# ServoController.net
KiCad netlist of a schematic drawn in Altium Designer
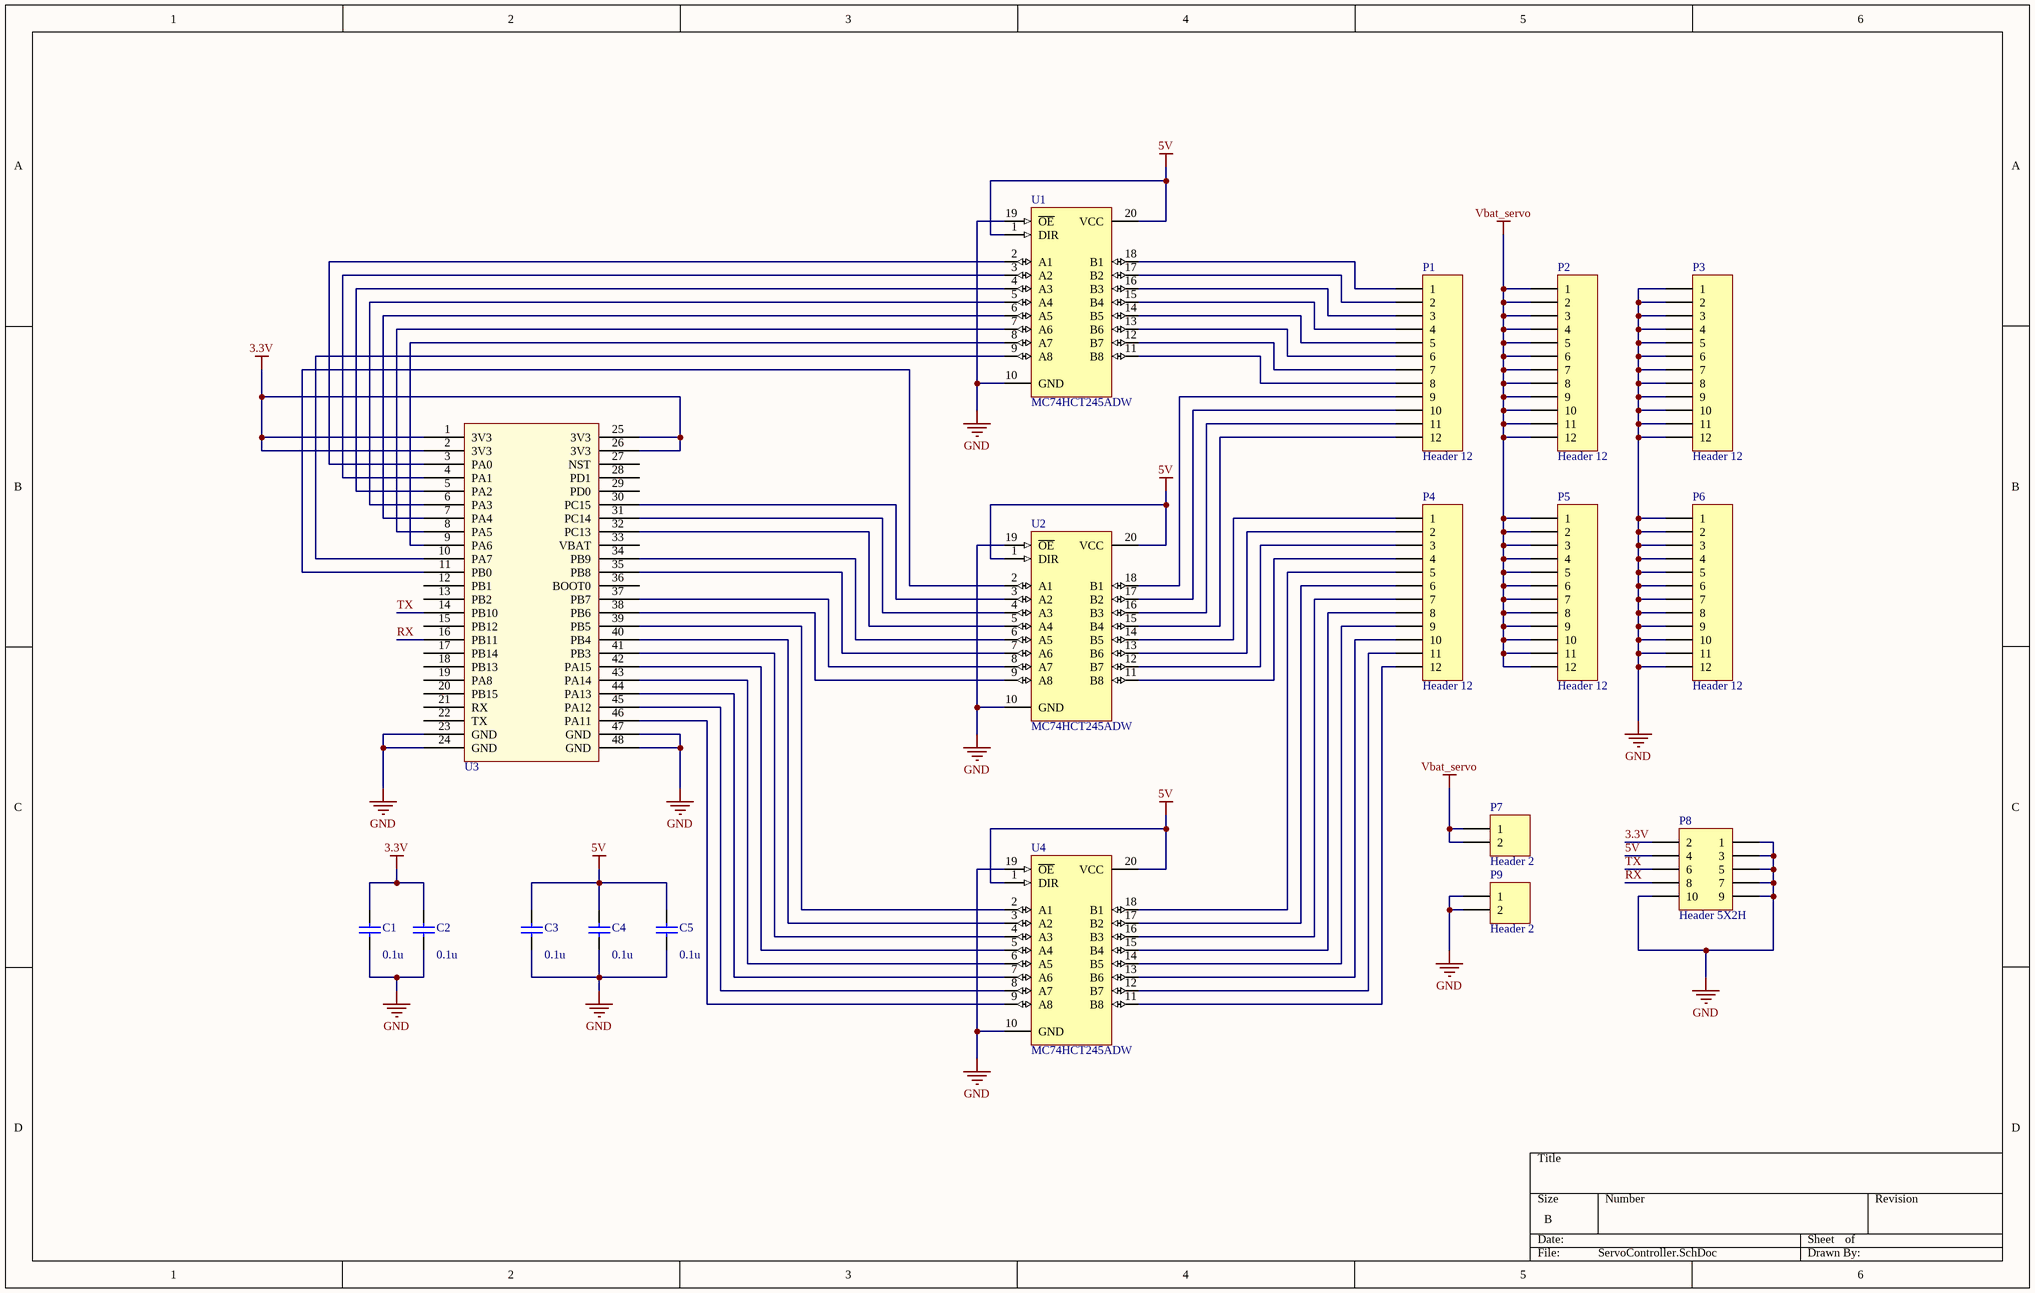
[diagram p0: ServoController.SchDoc]

(export (version "E")
  (design (tool "Eeschema 10.0.6"))
  (components
    (comp (ref "C1")
      (value "0.1u")
      (footprint "C1206")
      (description "Capacitor (Semiconductor SIM Model)")
      (fields (field (name "Comment") "Cap Semi") (field (name "PUBLISHER") "Altium Limited"))
      (libsource (lib "Miscellaneous Devices") (part "Cap Semi"))
    )
    (comp (ref "C2")
      (value "0.1u")
      (footprint "C1206")
      (description "Capacitor (Semiconductor SIM Model)")
      (fields (field (name "Comment") "Cap Semi") (field (name "PUBLISHER") "Altium Limited"))
      (libsource (lib "Miscellaneous Devices") (part "Cap Semi"))
    )
    (comp (ref "C3")
      (value "0.1u")
      (footprint "C1206")
      (description "Capacitor (Semiconductor SIM Model)")
      (fields (field (name "Comment") "Cap Semi") (field (name "PUBLISHER") "Altium Limited"))
      (libsource (lib "Miscellaneous Devices") (part "Cap Semi"))
    )
    (comp (ref "C4")
      (value "0.1u")
      (footprint "C1206")
      (description "Capacitor (Semiconductor SIM Model)")
      (fields (field (name "Comment") "Cap Semi") (field (name "PUBLISHER") "Altium Limited"))
      (libsource (lib "Miscellaneous Devices") (part "Cap Semi"))
    )
    (comp (ref "C5")
      (value "0.1u")
      (footprint "C1206")
      (description "Capacitor (Semiconductor SIM Model)")
      (fields (field (name "Comment") "Cap Semi") (field (name "PUBLISHER") "Altium Limited"))
      (libsource (lib "Miscellaneous Devices") (part "Cap Semi"))
    )
    (comp (ref "P1")
      (value "Header 12")
      (footprint "HDR1X12")
      (description "Header, 12-Pin")
      (fields (field (name "PUBLISHER") "Altium Limited"))
      (libsource (lib "Miscellaneous Connectors") (part "Header 12"))
    )
    (comp (ref "P2")
      (value "Header 12")
      (footprint "HDR1X12")
      (description "Header, 12-Pin")
      (fields (field (name "PUBLISHER") "Altium Limited"))
      (libsource (lib "Miscellaneous Connectors") (part "Header 12"))
    )
    (comp (ref "P3")
      (value "Header 12")
      (footprint "HDR1X12")
      (description "Header, 12-Pin")
      (fields (field (name "PUBLISHER") "Altium Limited"))
      (libsource (lib "Miscellaneous Connectors") (part "Header 12"))
    )
    (comp (ref "P4")
      (value "Header 12")
      (footprint "HDR1X12")
      (description "Header, 12-Pin")
      (fields (field (name "PUBLISHER") "Altium Limited"))
      (libsource (lib "Miscellaneous Connectors") (part "Header 12"))
    )
    (comp (ref "P5")
      (value "Header 12")
      (footprint "HDR1X12")
      (description "Header, 12-Pin")
      (fields (field (name "PUBLISHER") "Altium Limited"))
      (libsource (lib "Miscellaneous Connectors") (part "Header 12"))
    )
    (comp (ref "P6")
      (value "Header 12")
      (footprint "HDR1X12")
      (description "Header, 12-Pin")
      (fields (field (name "PUBLISHER") "Altium Limited"))
      (libsource (lib "Miscellaneous Connectors") (part "Header 12"))
    )
    (comp (ref "P7")
      (value "Header 2")
      (footprint "HDR1X2")
      (description "Header, 2-Pin")
      (fields (field (name "PUBLISHER") "Altium Limited"))
      (libsource (lib "Miscellaneous Connectors") (part "Header 2"))
    )
    (comp (ref "P8")
      (value "Header 5X2H")
      (footprint "HDR2X5H")
      (description "Header, 5-Pin, Dual row, Right Angle")
      (fields (field (name "PUBLISHER") "Altium Limited"))
      (libsource (lib "Miscellaneous Connectors") (part "Header 5X2H"))
    )
    (comp (ref "P9")
      (value "Header 2")
      (footprint "HDR1X2")
      (description "Header, 2-Pin")
      (fields (field (name "PUBLISHER") "Altium Limited"))
      (libsource (lib "Miscellaneous Connectors") (part "Header 2"))
    )
    (comp (ref "U1")
      (value "MC74HCT245ADW")
      (footprint "751D-05_N")
      (description "Octal 3-State Non-Inverting Bus Transceiver with LSTTL-Compatible Inputs")
      (fields (field (name "PUBLISHER") "Altium Limited"))
      (libsource (lib "ON Semi Interface Line Transceiver") (part "MC74HCT245ADW"))
    )
    (comp (ref "U2")
      (value "MC74HCT245ADW")
      (footprint "751D-05_N")
      (description "Octal 3-State Non-Inverting Bus Transceiver with LSTTL-Compatible Inputs")
      (fields (field (name "PUBLISHER") "Altium Limited"))
      (libsource (lib "ON Semi Interface Line Transceiver") (part "MC74HCT245ADW"))
    )
    (comp (ref "U3")
      (value "STM32F103C8T6_Module")
      (footprint "STM32F103C8T6_Module")
      (libsource (lib "QuadrupedSchLib") (part "STM32F103C8T6_Module"))
    )
    (comp (ref "U4")
      (value "MC74HCT245ADW")
      (footprint "751D-05_N")
      (description "Octal 3-State Non-Inverting Bus Transceiver with LSTTL-Compatible Inputs")
      (fields (field (name "PUBLISHER") "Altium Limited"))
      (libsource (lib "ON Semi Interface Line Transceiver") (part "MC74HCT245ADW"))
    )
  )
  (nets
    (net (code "1") (name "/RX") (class "Default")
      (node (ref "P8") (pin "8") (pinfunction "8_8") (pintype "passive"))
      (node (ref "U3") (pin "16") (pinfunction "PB11_16") (pintype "passive"))
    )
    (net (code "2") (name "/TX") (class "Default")
      (node (ref "P8") (pin "6") (pinfunction "6_6") (pintype "passive"))
      (node (ref "U3") (pin "14") (pinfunction "PB10_14") (pintype "passive"))
    )
    (net (code "3") (name "3.3V") (class "Default")
      (node (ref "C1") (pin "2") (pinfunction "2_2") (pintype "passive"))
      (node (ref "C2") (pin "2") (pinfunction "2_2") (pintype "passive"))
      (node (ref "P8") (pin "2") (pinfunction "2_2") (pintype "passive"))
      (node (ref "U3") (pin "1") (pinfunction "3V3_1") (pintype "passive"))
      (node (ref "U3") (pin "2") (pinfunction "3V3_2") (pintype "passive"))
      (node (ref "U3") (pin "25") (pinfunction "3V3_25") (pintype "passive"))
      (node (ref "U3") (pin "26") (pinfunction "3V3_26") (pintype "passive"))
    )
    (net (code "4") (name "5V") (class "Default")
      (node (ref "C3") (pin "2") (pinfunction "2_2") (pintype "passive"))
      (node (ref "C4") (pin "2") (pinfunction "2_2") (pintype "passive"))
      (node (ref "C5") (pin "2") (pinfunction "2_2") (pintype "passive"))
      (node (ref "P8") (pin "4") (pinfunction "4_4") (pintype "passive"))
      (node (ref "U1") (pin "1") (pinfunction "DIR_1") (pintype "input"))
      (node (ref "U1") (pin "20") (pinfunction "VCC_20") (pintype "power_in"))
      (node (ref "U2") (pin "1") (pinfunction "DIR_1") (pintype "input"))
      (node (ref "U2") (pin "20") (pinfunction "VCC_20") (pintype "power_in"))
      (node (ref "U4") (pin "1") (pinfunction "DIR_1") (pintype "input"))
      (node (ref "U4") (pin "20") (pinfunction "VCC_20") (pintype "power_in"))
    )
    (net (code "5") (name "GND") (class "Default")
      (node (ref "C1") (pin "1") (pinfunction "1_1") (pintype "passive"))
      (node (ref "C2") (pin "1") (pinfunction "1_1") (pintype "passive"))
      (node (ref "C3") (pin "1") (pinfunction "1_1") (pintype "passive"))
      (node (ref "C4") (pin "1") (pinfunction "1_1") (pintype "passive"))
      (node (ref "C5") (pin "1") (pinfunction "1_1") (pintype "passive"))
      (node (ref "P3") (pin "1") (pinfunction "1_1") (pintype "passive"))
      (node (ref "P3") (pin "10") (pinfunction "10_10") (pintype "passive"))
      (node (ref "P3") (pin "11") (pinfunction "11_11") (pintype "passive"))
      (node (ref "P3") (pin "12") (pinfunction "12_12") (pintype "passive"))
      (node (ref "P3") (pin "2") (pinfunction "2_2") (pintype "passive"))
      (node (ref "P3") (pin "3") (pinfunction "3_3") (pintype "passive"))
      (node (ref "P3") (pin "4") (pinfunction "4_4") (pintype "passive"))
      (node (ref "P3") (pin "5") (pinfunction "5_5") (pintype "passive"))
      (node (ref "P3") (pin "6") (pinfunction "6_6") (pintype "passive"))
      (node (ref "P3") (pin "7") (pinfunction "7_7") (pintype "passive"))
      (node (ref "P3") (pin "8") (pinfunction "8_8") (pintype "passive"))
      (node (ref "P3") (pin "9") (pinfunction "9_9") (pintype "passive"))
      (node (ref "P6") (pin "1") (pinfunction "1_1") (pintype "passive"))
      (node (ref "P6") (pin "10") (pinfunction "10_10") (pintype "passive"))
      (node (ref "P6") (pin "11") (pinfunction "11_11") (pintype "passive"))
      (node (ref "P6") (pin "12") (pinfunction "12_12") (pintype "passive"))
      (node (ref "P6") (pin "2") (pinfunction "2_2") (pintype "passive"))
      (node (ref "P6") (pin "3") (pinfunction "3_3") (pintype "passive"))
      (node (ref "P6") (pin "4") (pinfunction "4_4") (pintype "passive"))
      (node (ref "P6") (pin "5") (pinfunction "5_5") (pintype "passive"))
      (node (ref "P6") (pin "6") (pinfunction "6_6") (pintype "passive"))
      (node (ref "P6") (pin "7") (pinfunction "7_7") (pintype "passive"))
      (node (ref "P6") (pin "8") (pinfunction "8_8") (pintype "passive"))
      (node (ref "P6") (pin "9") (pinfunction "9_9") (pintype "passive"))
      (node (ref "P8") (pin "1") (pinfunction "1_1") (pintype "passive"))
      (node (ref "P8") (pin "10") (pinfunction "10_10") (pintype "passive"))
      (node (ref "P8") (pin "3") (pinfunction "3_3") (pintype "passive"))
      (node (ref "P8") (pin "5") (pinfunction "5_5") (pintype "passive"))
      (node (ref "P8") (pin "7") (pinfunction "7_7") (pintype "passive"))
      (node (ref "P8") (pin "9") (pinfunction "9_9") (pintype "passive"))
      (node (ref "P9") (pin "1") (pinfunction "1_1") (pintype "passive"))
      (node (ref "P9") (pin "2") (pinfunction "2_2") (pintype "passive"))
      (node (ref "U1") (pin "10") (pinfunction "GND_10") (pintype "power_in"))
      (node (ref "U1") (pin "19") (pinfunction "~{OE}_19") (pintype "input"))
      (node (ref "U2") (pin "10") (pinfunction "GND_10") (pintype "power_in"))
      (node (ref "U2") (pin "19") (pinfunction "~{OE}_19") (pintype "input"))
      (node (ref "U3") (pin "23") (pinfunction "GND_23") (pintype "passive"))
      (node (ref "U3") (pin "24") (pinfunction "GND_24") (pintype "passive"))
      (node (ref "U3") (pin "47") (pinfunction "GND_47") (pintype "passive"))
      (node (ref "U3") (pin "48") (pinfunction "GND_48") (pintype "passive"))
      (node (ref "U4") (pin "10") (pinfunction "GND_10") (pintype "power_in"))
      (node (ref "U4") (pin "19") (pinfunction "~{OE}_19") (pintype "input"))
    )
    (net (code "6") (name "Net-(U1-A1)") (class "Default")
      (node (ref "U1") (pin "2") (pinfunction "A1_2") (pintype "bidirectional"))
      (node (ref "U3") (pin "3") (pinfunction "PA0_3") (pintype "passive"))
    )
    (net (code "7") (name "Net-(U1-A2)") (class "Default")
      (node (ref "U1") (pin "3") (pinfunction "A2_3") (pintype "bidirectional"))
      (node (ref "U3") (pin "4") (pinfunction "PA1_4") (pintype "passive"))
    )
    (net (code "8") (name "Net-(U1-A3)") (class "Default")
      (node (ref "U1") (pin "4") (pinfunction "A3_4") (pintype "bidirectional"))
      (node (ref "U3") (pin "5") (pinfunction "PA2_5") (pintype "passive"))
    )
    (net (code "9") (name "Net-(U1-A4)") (class "Default")
      (node (ref "U1") (pin "5") (pinfunction "A4_5") (pintype "bidirectional"))
      (node (ref "U3") (pin "6") (pinfunction "PA3_6") (pintype "passive"))
    )
    (net (code "10") (name "Net-(U1-A5)") (class "Default")
      (node (ref "U1") (pin "6") (pinfunction "A5_6") (pintype "bidirectional"))
      (node (ref "U3") (pin "7") (pinfunction "PA4_7") (pintype "passive"))
    )
    (net (code "11") (name "Net-(U1-A6)") (class "Default")
      (node (ref "U1") (pin "7") (pinfunction "A6_7") (pintype "bidirectional"))
      (node (ref "U3") (pin "8") (pinfunction "PA5_8") (pintype "passive"))
    )
    (net (code "12") (name "Net-(U1-A7)") (class "Default")
      (node (ref "U1") (pin "8") (pinfunction "A7_8") (pintype "bidirectional"))
      (node (ref "U3") (pin "9") (pinfunction "PA6_9") (pintype "passive"))
    )
    (net (code "13") (name "Net-(U1-A8)") (class "Default")
      (node (ref "U1") (pin "9") (pinfunction "A8_9") (pintype "bidirectional"))
      (node (ref "U3") (pin "10") (pinfunction "PA7_10") (pintype "passive"))
    )
    (net (code "14") (name "Net-(U1-B1)") (class "Default")
      (node (ref "P1") (pin "1") (pinfunction "1_1") (pintype "passive"))
      (node (ref "U1") (pin "18") (pinfunction "B1_18") (pintype "bidirectional"))
    )
    (net (code "15") (name "Net-(U1-B2)") (class "Default")
      (node (ref "P1") (pin "2") (pinfunction "2_2") (pintype "passive"))
      (node (ref "U1") (pin "17") (pinfunction "B2_17") (pintype "bidirectional"))
    )
    (net (code "16") (name "Net-(U1-B3)") (class "Default")
      (node (ref "P1") (pin "3") (pinfunction "3_3") (pintype "passive"))
      (node (ref "U1") (pin "16") (pinfunction "B3_16") (pintype "bidirectional"))
    )
    (net (code "17") (name "Net-(U1-B4)") (class "Default")
      (node (ref "P1") (pin "4") (pinfunction "4_4") (pintype "passive"))
      (node (ref "U1") (pin "15") (pinfunction "B4_15") (pintype "bidirectional"))
    )
    (net (code "18") (name "Net-(U1-B5)") (class "Default")
      (node (ref "P1") (pin "5") (pinfunction "5_5") (pintype "passive"))
      (node (ref "U1") (pin "14") (pinfunction "B5_14") (pintype "bidirectional"))
    )
    (net (code "19") (name "Net-(U1-B6)") (class "Default")
      (node (ref "P1") (pin "6") (pinfunction "6_6") (pintype "passive"))
      (node (ref "U1") (pin "13") (pinfunction "B6_13") (pintype "bidirectional"))
    )
    (net (code "20") (name "Net-(U1-B7)") (class "Default")
      (node (ref "P1") (pin "7") (pinfunction "7_7") (pintype "passive"))
      (node (ref "U1") (pin "12") (pinfunction "B7_12") (pintype "bidirectional"))
    )
    (net (code "21") (name "Net-(U1-B8)") (class "Default")
      (node (ref "P1") (pin "8") (pinfunction "8_8") (pintype "passive"))
      (node (ref "U1") (pin "11") (pinfunction "B8_11") (pintype "bidirectional"))
    )
    (net (code "22") (name "Net-(U2-A1)") (class "Default")
      (node (ref "U2") (pin "2") (pinfunction "A1_2") (pintype "bidirectional"))
      (node (ref "U3") (pin "11") (pinfunction "PB0_11") (pintype "passive"))
    )
    (net (code "23") (name "Net-(U2-A2)") (class "Default")
      (node (ref "U2") (pin "3") (pinfunction "A2_3") (pintype "bidirectional"))
      (node (ref "U3") (pin "30") (pinfunction "PC15_30") (pintype "passive"))
    )
    (net (code "24") (name "Net-(U2-A3)") (class "Default")
      (node (ref "U2") (pin "4") (pinfunction "A3_4") (pintype "bidirectional"))
      (node (ref "U3") (pin "31") (pinfunction "PC14_31") (pintype "passive"))
    )
    (net (code "25") (name "Net-(U2-A4)") (class "Default")
      (node (ref "U2") (pin "5") (pinfunction "A4_5") (pintype "bidirectional"))
      (node (ref "U3") (pin "32") (pinfunction "PC13_32") (pintype "passive"))
    )
    (net (code "26") (name "Net-(U2-A5)") (class "Default")
      (node (ref "U2") (pin "6") (pinfunction "A5_6") (pintype "bidirectional"))
      (node (ref "U3") (pin "34") (pinfunction "PB9_34") (pintype "passive"))
    )
    (net (code "27") (name "Net-(U2-A6)") (class "Default")
      (node (ref "U2") (pin "7") (pinfunction "A6_7") (pintype "bidirectional"))
      (node (ref "U3") (pin "35") (pinfunction "PB8_35") (pintype "passive"))
    )
    (net (code "28") (name "Net-(U2-A7)") (class "Default")
      (node (ref "U2") (pin "8") (pinfunction "A7_8") (pintype "bidirectional"))
      (node (ref "U3") (pin "37") (pinfunction "PB7_37") (pintype "passive"))
    )
    (net (code "29") (name "Net-(U2-A8)") (class "Default")
      (node (ref "U2") (pin "9") (pinfunction "A8_9") (pintype "bidirectional"))
      (node (ref "U3") (pin "38") (pinfunction "PB6_38") (pintype "passive"))
    )
    (net (code "30") (name "Net-(U2-B1)") (class "Default")
      (node (ref "P1") (pin "9") (pinfunction "9_9") (pintype "passive"))
      (node (ref "U2") (pin "18") (pinfunction "B1_18") (pintype "bidirectional"))
    )
    (net (code "31") (name "Net-(U2-B2)") (class "Default")
      (node (ref "P1") (pin "10") (pinfunction "10_10") (pintype "passive"))
      (node (ref "U2") (pin "17") (pinfunction "B2_17") (pintype "bidirectional"))
    )
    (net (code "32") (name "Net-(U2-B3)") (class "Default")
      (node (ref "P1") (pin "11") (pinfunction "11_11") (pintype "passive"))
      (node (ref "U2") (pin "16") (pinfunction "B3_16") (pintype "bidirectional"))
    )
    (net (code "33") (name "Net-(U2-B4)") (class "Default")
      (node (ref "P1") (pin "12") (pinfunction "12_12") (pintype "passive"))
      (node (ref "U2") (pin "15") (pinfunction "B4_15") (pintype "bidirectional"))
    )
    (net (code "34") (name "Net-(U2-B5)") (class "Default")
      (node (ref "P4") (pin "1") (pinfunction "1_1") (pintype "passive"))
      (node (ref "U2") (pin "14") (pinfunction "B5_14") (pintype "bidirectional"))
    )
    (net (code "35") (name "Net-(U2-B6)") (class "Default")
      (node (ref "P4") (pin "2") (pinfunction "2_2") (pintype "passive"))
      (node (ref "U2") (pin "13") (pinfunction "B6_13") (pintype "bidirectional"))
    )
    (net (code "36") (name "Net-(U2-B7)") (class "Default")
      (node (ref "P4") (pin "3") (pinfunction "3_3") (pintype "passive"))
      (node (ref "U2") (pin "12") (pinfunction "B7_12") (pintype "bidirectional"))
    )
    (net (code "37") (name "Net-(U2-B8)") (class "Default")
      (node (ref "P4") (pin "4") (pinfunction "4_4") (pintype "passive"))
      (node (ref "U2") (pin "11") (pinfunction "B8_11") (pintype "bidirectional"))
    )
    (net (code "38") (name "Net-(U3-PA11)") (class "Default")
      (node (ref "U3") (pin "46") (pinfunction "PA11_46") (pintype "passive"))
      (node (ref "U4") (pin "9") (pinfunction "A8_9") (pintype "bidirectional"))
    )
    (net (code "39") (name "Net-(U3-PA12)") (class "Default")
      (node (ref "U3") (pin "45") (pinfunction "PA12_45") (pintype "passive"))
      (node (ref "U4") (pin "8") (pinfunction "A7_8") (pintype "bidirectional"))
    )
    (net (code "40") (name "Net-(U3-PA13)") (class "Default")
      (node (ref "U3") (pin "44") (pinfunction "PA13_44") (pintype "passive"))
      (node (ref "U4") (pin "7") (pinfunction "A6_7") (pintype "bidirectional"))
    )
    (net (code "41") (name "Net-(U3-PA14)") (class "Default")
      (node (ref "U3") (pin "43") (pinfunction "PA14_43") (pintype "passive"))
      (node (ref "U4") (pin "6") (pinfunction "A5_6") (pintype "bidirectional"))
    )
    (net (code "42") (name "Net-(U3-PA15)") (class "Default")
      (node (ref "U3") (pin "42") (pinfunction "PA15_42") (pintype "passive"))
      (node (ref "U4") (pin "5") (pinfunction "A4_5") (pintype "bidirectional"))
    )
    (net (code "43") (name "Net-(U3-PB3)") (class "Default")
      (node (ref "U3") (pin "41") (pinfunction "PB3_41") (pintype "passive"))
      (node (ref "U4") (pin "4") (pinfunction "A3_4") (pintype "bidirectional"))
    )
    (net (code "44") (name "Net-(U3-PB4)") (class "Default")
      (node (ref "U3") (pin "40") (pinfunction "PB4_40") (pintype "passive"))
      (node (ref "U4") (pin "3") (pinfunction "A2_3") (pintype "bidirectional"))
    )
    (net (code "45") (name "Net-(U3-PB5)") (class "Default")
      (node (ref "U3") (pin "39") (pinfunction "PB5_39") (pintype "passive"))
      (node (ref "U4") (pin "2") (pinfunction "A1_2") (pintype "bidirectional"))
    )
    (net (code "46") (name "Net-(U4-B1)") (class "Default")
      (node (ref "P4") (pin "5") (pinfunction "5_5") (pintype "passive"))
      (node (ref "U4") (pin "18") (pinfunction "B1_18") (pintype "bidirectional"))
    )
    (net (code "47") (name "Net-(U4-B2)") (class "Default")
      (node (ref "P4") (pin "6") (pinfunction "6_6") (pintype "passive"))
      (node (ref "U4") (pin "17") (pinfunction "B2_17") (pintype "bidirectional"))
    )
    (net (code "48") (name "Net-(U4-B3)") (class "Default")
      (node (ref "P4") (pin "7") (pinfunction "7_7") (pintype "passive"))
      (node (ref "U4") (pin "16") (pinfunction "B3_16") (pintype "bidirectional"))
    )
    (net (code "49") (name "Net-(U4-B4)") (class "Default")
      (node (ref "P4") (pin "8") (pinfunction "8_8") (pintype "passive"))
      (node (ref "U4") (pin "15") (pinfunction "B4_15") (pintype "bidirectional"))
    )
    (net (code "50") (name "Net-(U4-B5)") (class "Default")
      (node (ref "P4") (pin "9") (pinfunction "9_9") (pintype "passive"))
      (node (ref "U4") (pin "14") (pinfunction "B5_14") (pintype "bidirectional"))
    )
    (net (code "51") (name "Net-(U4-B6)") (class "Default")
      (node (ref "P4") (pin "10") (pinfunction "10_10") (pintype "passive"))
      (node (ref "U4") (pin "13") (pinfunction "B6_13") (pintype "bidirectional"))
    )
    (net (code "52") (name "Net-(U4-B7)") (class "Default")
      (node (ref "P4") (pin "11") (pinfunction "11_11") (pintype "passive"))
      (node (ref "U4") (pin "12") (pinfunction "B7_12") (pintype "bidirectional"))
    )
    (net (code "53") (name "Net-(U4-B8)") (class "Default")
      (node (ref "P4") (pin "12") (pinfunction "12_12") (pintype "passive"))
      (node (ref "U4") (pin "11") (pinfunction "B8_11") (pintype "bidirectional"))
    )
    (net (code "54") (name "Vbat_servo") (class "Default")
      (node (ref "P2") (pin "1") (pinfunction "1_1") (pintype "passive"))
      (node (ref "P2") (pin "10") (pinfunction "10_10") (pintype "passive"))
      (node (ref "P2") (pin "11") (pinfunction "11_11") (pintype "passive"))
      (node (ref "P2") (pin "12") (pinfunction "12_12") (pintype "passive"))
      (node (ref "P2") (pin "2") (pinfunction "2_2") (pintype "passive"))
      (node (ref "P2") (pin "3") (pinfunction "3_3") (pintype "passive"))
      (node (ref "P2") (pin "4") (pinfunction "4_4") (pintype "passive"))
      (node (ref "P2") (pin "5") (pinfunction "5_5") (pintype "passive"))
      (node (ref "P2") (pin "6") (pinfunction "6_6") (pintype "passive"))
      (node (ref "P2") (pin "7") (pinfunction "7_7") (pintype "passive"))
      (node (ref "P2") (pin "8") (pinfunction "8_8") (pintype "passive"))
      (node (ref "P2") (pin "9") (pinfunction "9_9") (pintype "passive"))
      (node (ref "P5") (pin "1") (pinfunction "1_1") (pintype "passive"))
      (node (ref "P5") (pin "10") (pinfunction "10_10") (pintype "passive"))
      (node (ref "P5") (pin "11") (pinfunction "11_11") (pintype "passive"))
      (node (ref "P5") (pin "12") (pinfunction "12_12") (pintype "passive"))
      (node (ref "P5") (pin "2") (pinfunction "2_2") (pintype "passive"))
      (node (ref "P5") (pin "3") (pinfunction "3_3") (pintype "passive"))
      (node (ref "P5") (pin "4") (pinfunction "4_4") (pintype "passive"))
      (node (ref "P5") (pin "5") (pinfunction "5_5") (pintype "passive"))
      (node (ref "P5") (pin "6") (pinfunction "6_6") (pintype "passive"))
      (node (ref "P5") (pin "7") (pinfunction "7_7") (pintype "passive"))
      (node (ref "P5") (pin "8") (pinfunction "8_8") (pintype "passive"))
      (node (ref "P5") (pin "9") (pinfunction "9_9") (pintype "passive"))
      (node (ref "P7") (pin "1") (pinfunction "1_1") (pintype "passive"))
      (node (ref "P7") (pin "2") (pinfunction "2_2") (pintype "passive"))
    )
    (net (code "55") (name "unconnected-(U3-BOOT0-Pad36)") (class "Default")
      (node (ref "U3") (pin "36") (pinfunction "BOOT0_36") (pintype "passive"))
    )
    (net (code "56") (name "unconnected-(U3-NST-Pad27)") (class "Default")
      (node (ref "U3") (pin "27") (pinfunction "NST_27") (pintype "passive"))
    )
    (net (code "57") (name "unconnected-(U3-PA8-Pad19)") (class "Default")
      (node (ref "U3") (pin "19") (pinfunction "PA8_19") (pintype "passive"))
    )
    (net (code "58") (name "unconnected-(U3-PB1-Pad12)") (class "Default")
      (node (ref "U3") (pin "12") (pinfunction "PB1_12") (pintype "passive"))
    )
    (net (code "59") (name "unconnected-(U3-PB2-Pad13)") (class "Default")
      (node (ref "U3") (pin "13") (pinfunction "PB2_13") (pintype "passive"))
    )
    (net (code "60") (name "unconnected-(U3-PB12-Pad15)") (class "Default")
      (node (ref "U3") (pin "15") (pinfunction "PB12_15") (pintype "passive"))
    )
    (net (code "61") (name "unconnected-(U3-PB13-Pad18)") (class "Default")
      (node (ref "U3") (pin "18") (pinfunction "PB13_18") (pintype "passive"))
    )
    (net (code "62") (name "unconnected-(U3-PB14-Pad17)") (class "Default")
      (node (ref "U3") (pin "17") (pinfunction "PB14_17") (pintype "passive"))
    )
    (net (code "63") (name "unconnected-(U3-PB15-Pad20)") (class "Default")
      (node (ref "U3") (pin "20") (pinfunction "PB15_20") (pintype "passive"))
    )
    (net (code "64") (name "unconnected-(U3-PD0-Pad29)") (class "Default")
      (node (ref "U3") (pin "29") (pinfunction "PD0_29") (pintype "passive"))
    )
    (net (code "65") (name "unconnected-(U3-PD1-Pad28)") (class "Default")
      (node (ref "U3") (pin "28") (pinfunction "PD1_28") (pintype "passive"))
    )
    (net (code "66") (name "unconnected-(U3-RX-Pad21)") (class "Default")
      (node (ref "U3") (pin "21") (pinfunction "RX_21") (pintype "passive"))
    )
    (net (code "67") (name "unconnected-(U3-TX-Pad22)") (class "Default")
      (node (ref "U3") (pin "22") (pinfunction "TX_22") (pintype "passive"))
    )
    (net (code "68") (name "unconnected-(U3-VBAT-Pad33)") (class "Default")
      (node (ref "U3") (pin "33") (pinfunction "VBAT_33") (pintype "passive"))
    )
  )
)
